# M703E.net
KiCad netlist of a schematic drawn in EAGLE
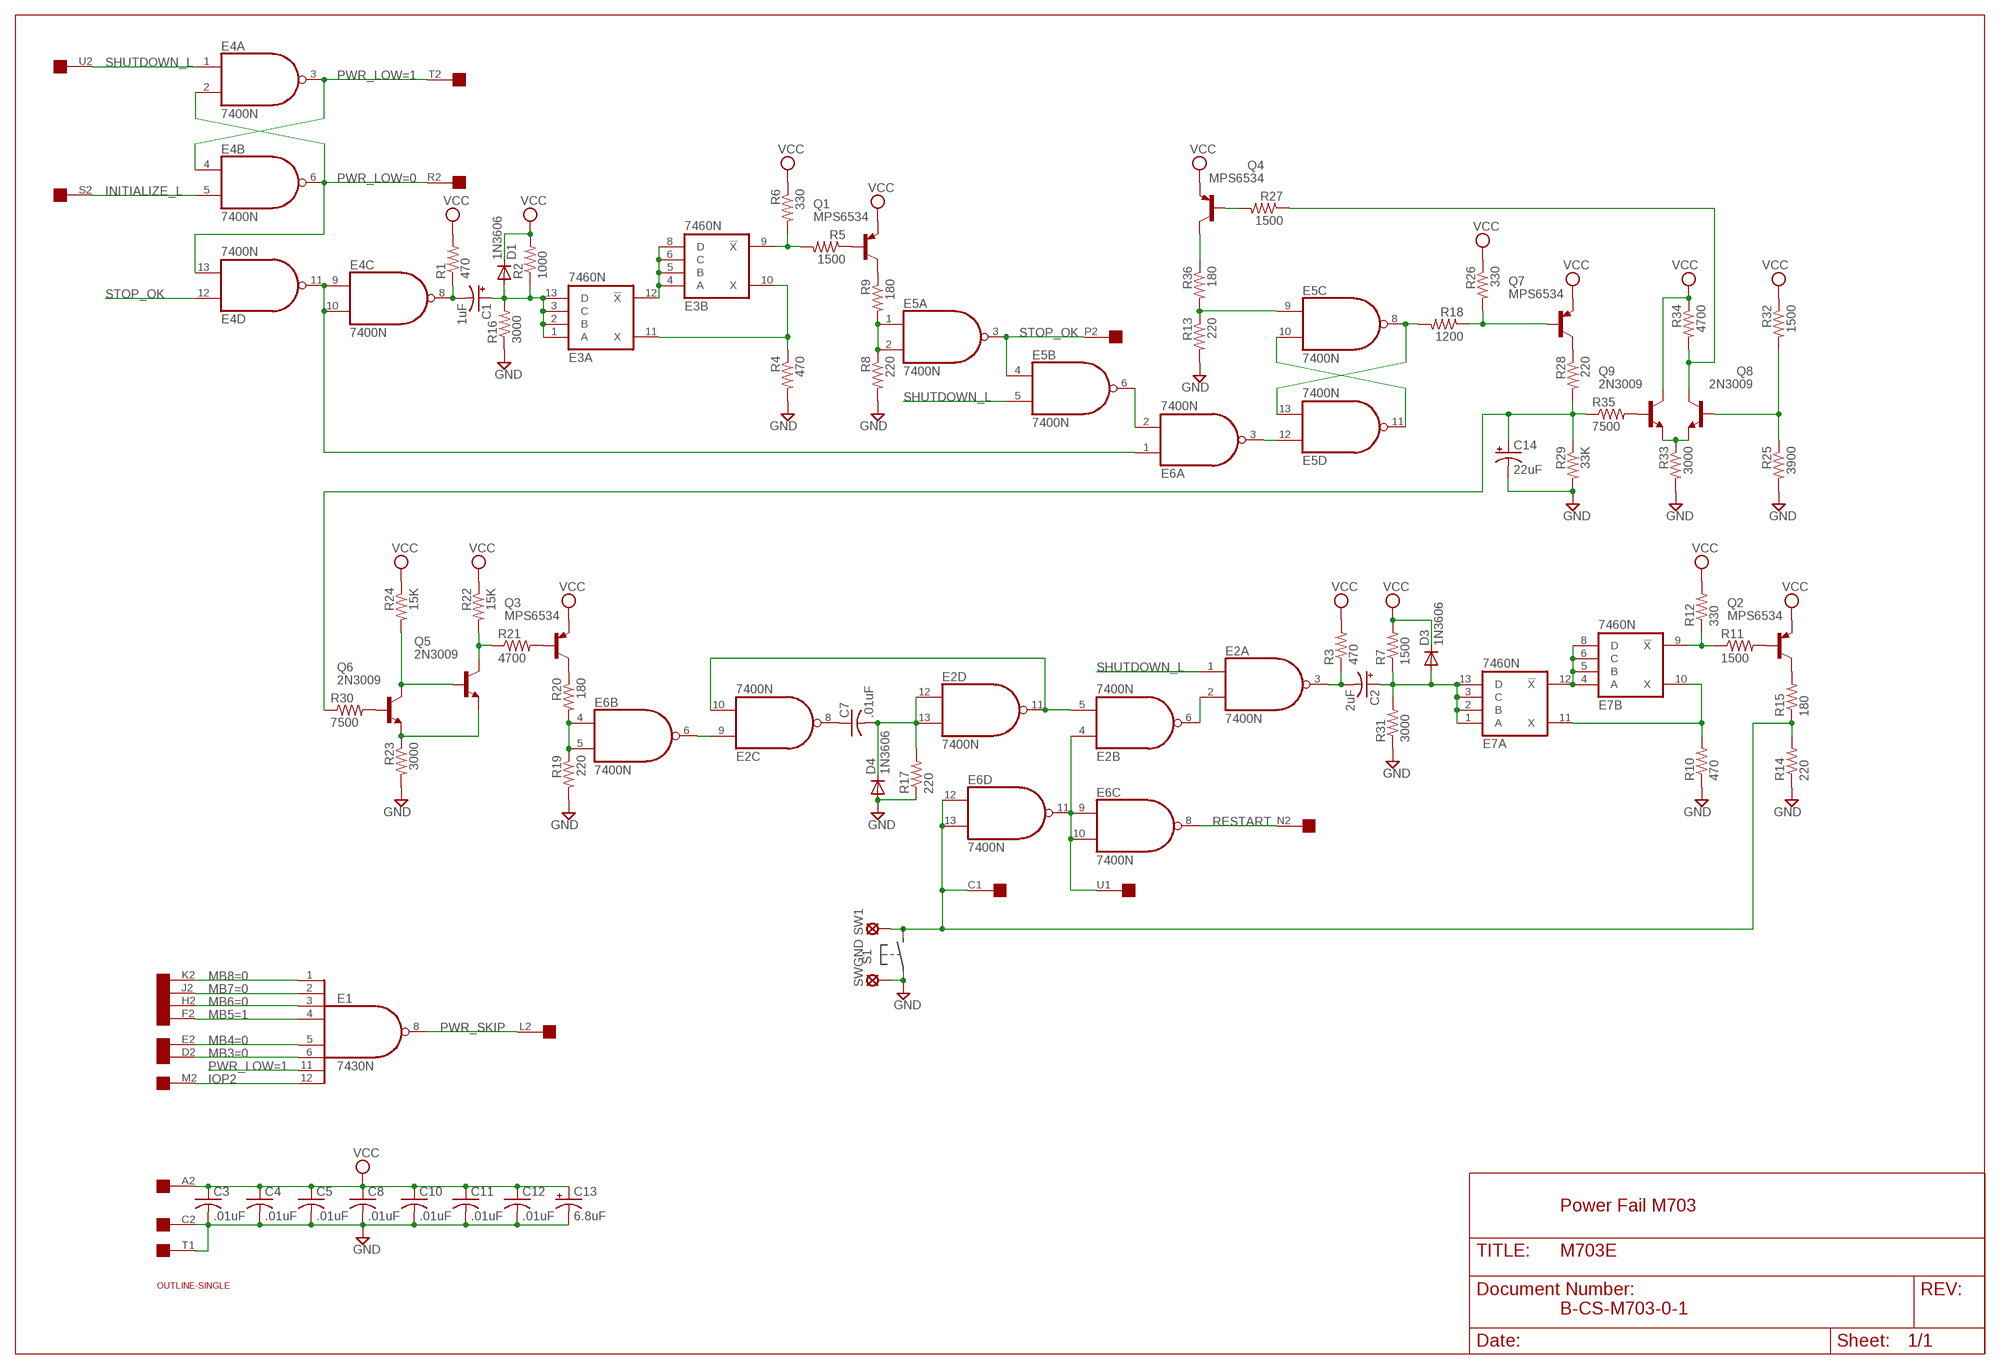
[diagram p0: schematic, sheet 1]

(export (version "E")
  (design (tool "Eeschema 10.0.6"))
  (components
    (comp (ref "C1")
      (value "1uF")
      (footprint "eagle-import:E12-4")
      (libsource (lib "eagle-import") (part "CPOL-USE12-4AXIAL"))
    )
    (comp (ref "C2")
      (value "2uF")
      (footprint "eagle-import:E12-4")
      (libsource (lib "eagle-import") (part "CPOL-USE12-4AXIAL"))
    )
    (comp (ref "C3")
      (value ".01uF")
      (footprint "eagle-import:C050-025X075")
      (libsource (lib "eagle-import") (part "C-US050-025X075"))
    )
    (comp (ref "C4")
      (value ".01uF")
      (footprint "eagle-import:C050-025X075")
      (libsource (lib "eagle-import") (part "C-US050-025X075"))
    )
    (comp (ref "C5")
      (value ".01uF")
      (footprint "eagle-import:C050-025X075")
      (libsource (lib "eagle-import") (part "C-US050-025X075"))
    )
    (comp (ref "C7")
      (value ".01uF")
      (footprint "eagle-import:C050-025X075")
      (libsource (lib "eagle-import") (part "C-US050-025X075"))
    )
    (comp (ref "C8")
      (value ".01uF")
      (footprint "eagle-import:C050-025X075")
      (libsource (lib "eagle-import") (part "C-US050-025X075"))
    )
    (comp (ref "C10")
      (value ".01uF")
      (footprint "eagle-import:C050-025X075")
      (libsource (lib "eagle-import") (part "C-US050-025X075"))
    )
    (comp (ref "C11")
      (value ".01uF")
      (footprint "eagle-import:C050-025X075")
      (libsource (lib "eagle-import") (part "C-US050-025X075"))
    )
    (comp (ref "C12")
      (value ".01uF")
      (footprint "eagle-import:C050-025X075")
      (libsource (lib "eagle-import") (part "C-US050-025X075"))
    )
    (comp (ref "C13")
      (value "6.8uF")
      (footprint "eagle-import:E15-5")
      (libsource (lib "eagle-import") (part "CPOL-USE15-5AXIAL"))
    )
    (comp (ref "C14")
      (value "22uF")
      (footprint "eagle-import:E15-5")
      (libsource (lib "eagle-import") (part "CPOL-USE15-5AXIAL"))
    )
    (comp (ref "D1")
      (value "1N3606")
      (footprint "eagle-import:DO35-10")
      (libsource (lib "eagle-import") (part "1N4148DO35-10"))
    )
    (comp (ref "D3")
      (value "1N3606")
      (footprint "eagle-import:DO35-10")
      (libsource (lib "eagle-import") (part "1N4148DO35-10"))
    )
    (comp (ref "D4")
      (value "1N3606")
      (footprint "eagle-import:DO35-10")
      (libsource (lib "eagle-import") (part "1N4148DO35-10"))
    )
    (comp (ref "E1")
      (value "7430N")
      (footprint "eagle-import:DIL14")
      (libsource (lib "eagle-import") (part "7430N"))
    )
    (comp (ref "E2")
      (value "7400N")
      (footprint "eagle-import:DIL14")
      (libsource (lib "eagle-import") (part "7400N"))
    )
    (comp (ref "E3")
      (value "7460N")
      (footprint "eagle-import:DIL14")
      (libsource (lib "eagle-import") (part "7460N"))
    )
    (comp (ref "E4")
      (value "7400N")
      (footprint "eagle-import:DIL14")
      (libsource (lib "eagle-import") (part "7400N"))
    )
    (comp (ref "E5")
      (value "7400N")
      (footprint "eagle-import:DIL14")
      (libsource (lib "eagle-import") (part "7400N"))
    )
    (comp (ref "E6")
      (value "7400N")
      (footprint "eagle-import:DIL14")
      (libsource (lib "eagle-import") (part "7400N"))
    )
    (comp (ref "E7")
      (value "7460N")
      (footprint "eagle-import:DIL14")
      (libsource (lib "eagle-import") (part "7460N"))
    )
    (comp (ref "Q1")
      (value "MPS6534")
      (footprint "eagle-import:TO39")
      (libsource (lib "eagle-import") (part "2N2904"))
    )
    (comp (ref "Q2")
      (value "MPS6534")
      (footprint "eagle-import:TO39")
      (libsource (lib "eagle-import") (part "2N2904"))
    )
    (comp (ref "Q3")
      (value "MPS6534")
      (footprint "eagle-import:TO39")
      (libsource (lib "eagle-import") (part "2N2904"))
    )
    (comp (ref "Q4")
      (value "MPS6534")
      (footprint "eagle-import:TO39")
      (libsource (lib "eagle-import") (part "2N2904"))
    )
    (comp (ref "Q5")
      (value "2N3009")
      (footprint "eagle-import:TO5")
      (libsource (lib "eagle-import") (part "2N2219"))
    )
    (comp (ref "Q6")
      (value "2N3009")
      (footprint "eagle-import:TO5")
      (libsource (lib "eagle-import") (part "2N2219"))
    )
    (comp (ref "Q7")
      (value "MPS6534")
      (footprint "eagle-import:TO39")
      (libsource (lib "eagle-import") (part "2N2904"))
    )
    (comp (ref "Q8")
      (value "2N3009")
      (footprint "eagle-import:TO5")
      (libsource (lib "eagle-import") (part "2N2219"))
    )
    (comp (ref "Q9")
      (value "2N3009")
      (footprint "eagle-import:TO5")
      (libsource (lib "eagle-import") (part "2N2219"))
    )
    (comp (ref "R1")
      (value "470")
      (footprint "eagle-import:0207_10")
      (libsource (lib "eagle-import") (part "R-US_0207/10"))
    )
    (comp (ref "R2")
      (value "1000")
      (footprint "eagle-import:0207_10")
      (libsource (lib "eagle-import") (part "R-US_0207/10"))
    )
    (comp (ref "R3")
      (value "470")
      (footprint "eagle-import:0207_10")
      (libsource (lib "eagle-import") (part "R-US_0207/10"))
    )
    (comp (ref "R4")
      (value "470")
      (footprint "eagle-import:0207_10")
      (libsource (lib "eagle-import") (part "R-US_0207/10"))
    )
    (comp (ref "R5")
      (value "1500")
      (footprint "eagle-import:0207_10")
      (libsource (lib "eagle-import") (part "R-US_0207/10"))
    )
    (comp (ref "R6")
      (value "330")
      (footprint "eagle-import:0207_10")
      (libsource (lib "eagle-import") (part "R-US_0207/10"))
    )
    (comp (ref "R7")
      (value "1500")
      (footprint "eagle-import:0207_10")
      (libsource (lib "eagle-import") (part "R-US_0207/10"))
    )
    (comp (ref "R8")
      (value "220")
      (footprint "eagle-import:0207_10")
      (libsource (lib "eagle-import") (part "R-US_0207/10"))
    )
    (comp (ref "R9")
      (value "180")
      (footprint "eagle-import:0207_10")
      (libsource (lib "eagle-import") (part "R-US_0207/10"))
    )
    (comp (ref "R10")
      (value "470")
      (footprint "eagle-import:0207_10")
      (libsource (lib "eagle-import") (part "R-US_0207/10"))
    )
    (comp (ref "R11")
      (value "1500")
      (footprint "eagle-import:0207_10")
      (libsource (lib "eagle-import") (part "R-US_0207/10"))
    )
    (comp (ref "R12")
      (value "330")
      (footprint "eagle-import:0207_10")
      (libsource (lib "eagle-import") (part "R-US_0207/10"))
    )
    (comp (ref "R13")
      (value "220")
      (footprint "eagle-import:0207_10")
      (libsource (lib "eagle-import") (part "R-US_0207/10"))
    )
    (comp (ref "R14")
      (value "220")
      (footprint "eagle-import:0207_10")
      (libsource (lib "eagle-import") (part "R-US_0207/10"))
    )
    (comp (ref "R15")
      (value "180")
      (footprint "eagle-import:0207_10")
      (libsource (lib "eagle-import") (part "R-US_0207/10"))
    )
    (comp (ref "R16")
      (value "3000")
      (footprint "eagle-import:0207_10")
      (libsource (lib "eagle-import") (part "R-US_0207/10"))
    )
    (comp (ref "R17")
      (value "220")
      (footprint "eagle-import:0207_10")
      (libsource (lib "eagle-import") (part "R-US_0207/10"))
    )
    (comp (ref "R18")
      (value "1200")
      (footprint "eagle-import:0207_10")
      (libsource (lib "eagle-import") (part "R-US_0207/10"))
    )
    (comp (ref "R19")
      (value "220")
      (footprint "eagle-import:0207_10")
      (libsource (lib "eagle-import") (part "R-US_0207/10"))
    )
    (comp (ref "R20")
      (value "180")
      (footprint "eagle-import:0207_10")
      (libsource (lib "eagle-import") (part "R-US_0207/10"))
    )
    (comp (ref "R21")
      (value "4700")
      (footprint "eagle-import:0207_10")
      (libsource (lib "eagle-import") (part "R-US_0207/10"))
    )
    (comp (ref "R22")
      (value "15K")
      (footprint "eagle-import:0207_10")
      (libsource (lib "eagle-import") (part "R-US_0207/10"))
    )
    (comp (ref "R23")
      (value "3000")
      (footprint "eagle-import:0207_10")
      (libsource (lib "eagle-import") (part "R-US_0207/10"))
    )
    (comp (ref "R24")
      (value "15K")
      (footprint "eagle-import:0207_10")
      (libsource (lib "eagle-import") (part "R-US_0207/10"))
    )
    (comp (ref "R25")
      (value "3900")
      (footprint "eagle-import:0207_10")
      (libsource (lib "eagle-import") (part "R-US_0207/10"))
    )
    (comp (ref "R26")
      (value "330")
      (footprint "eagle-import:0207_10")
      (libsource (lib "eagle-import") (part "R-US_0207/10"))
    )
    (comp (ref "R27")
      (value "1500")
      (footprint "eagle-import:0207_10")
      (libsource (lib "eagle-import") (part "R-US_0207/10"))
    )
    (comp (ref "R28")
      (value "220")
      (footprint "eagle-import:0207_10")
      (libsource (lib "eagle-import") (part "R-US_0207/10"))
    )
    (comp (ref "R29")
      (value "33K")
      (footprint "eagle-import:0207_10")
      (libsource (lib "eagle-import") (part "R-US_0207/10"))
    )
    (comp (ref "R30")
      (value "7500")
      (footprint "eagle-import:0207_10")
      (libsource (lib "eagle-import") (part "R-US_0207/10"))
    )
    (comp (ref "R31")
      (value "3000")
      (footprint "eagle-import:0207_10")
      (libsource (lib "eagle-import") (part "R-US_0207/10"))
    )
    (comp (ref "R32")
      (value "1500")
      (footprint "eagle-import:0207_10")
      (libsource (lib "eagle-import") (part "R-US_0207/10"))
    )
    (comp (ref "R33")
      (value "3000")
      (footprint "eagle-import:0207_10")
      (libsource (lib "eagle-import") (part "R-US_0207/10"))
    )
    (comp (ref "R34")
      (value "4700")
      (footprint "eagle-import:0207_10")
      (libsource (lib "eagle-import") (part "R-US_0207/10"))
    )
    (comp (ref "R35")
      (value "7500")
      (footprint "eagle-import:0207_10")
      (libsource (lib "eagle-import") (part "R-US_0207/10"))
    )
    (comp (ref "R36")
      (value "180")
      (footprint "eagle-import:0207_10")
      (libsource (lib "eagle-import") (part "R-US_0207/10"))
    )
    (comp (ref "SW1")
      (value "SE14")
      (footprint "eagle-import:SE14")
      (libsource (lib "eagle-import") (part "SE14"))
    )
    (comp (ref "SWGND")
      (value "SE14")
      (footprint "eagle-import:SE14")
      (libsource (lib "eagle-import") (part "SE14"))
    )
    (comp (ref "U$2")
      (value "SINGLE")
      (footprint "eagle-import:EDGE-CON2")
      (libsource (lib "eagle-import") (part "SINGLE"))
    )
    (comp (ref "U$4")
      (value "OUTLINE-SINGLE")
      (footprint "eagle-import:SINGLE")
      (libsource (lib "eagle-import") (part "OUTLINE-SINGLE"))
    )
  )
  (nets
    (net (code "1") (name "/INITIALIZE_L") (class "Default")
      (node (ref "E4") (pin "5") (pinfunction "I1_5") (pintype "input"))
      (node (ref "U$2") (pin "S2") (pinfunction "1_S2") (pintype "bidirectional"))
    )
    (net (code "2") (name "/IOP2") (class "Default")
      (node (ref "E1") (pin "12") (pinfunction "I7_12") (pintype "input"))
      (node (ref "U$2") (pin "M2") (pinfunction "1_M2") (pintype "bidirectional"))
    )
    (net (code "3") (name "/MB3=0") (class "Default")
      (node (ref "E1") (pin "6") (pinfunction "I5_6") (pintype "input"))
      (node (ref "U$2") (pin "D2") (pinfunction "1_D2") (pintype "bidirectional"))
    )
    (net (code "4") (name "/MB4=0") (class "Default")
      (node (ref "E1") (pin "5") (pinfunction "I4_5") (pintype "input"))
      (node (ref "U$2") (pin "E2") (pinfunction "1_E2") (pintype "bidirectional"))
    )
    (net (code "5") (name "/MB5=1") (class "Default")
      (node (ref "E1") (pin "4") (pinfunction "I3_4") (pintype "input"))
      (node (ref "U$2") (pin "F2") (pinfunction "1_F2") (pintype "bidirectional"))
    )
    (net (code "6") (name "/MB6=0") (class "Default")
      (node (ref "E1") (pin "3") (pinfunction "I2_3") (pintype "input"))
      (node (ref "U$2") (pin "H2") (pinfunction "1_H2") (pintype "bidirectional"))
    )
    (net (code "7") (name "/MB7=0") (class "Default")
      (node (ref "E1") (pin "2") (pinfunction "I1_2") (pintype "input"))
      (node (ref "U$2") (pin "J2") (pinfunction "1_J2") (pintype "bidirectional"))
    )
    (net (code "8") (name "/MB8=0") (class "Default")
      (node (ref "E1") (pin "1") (pinfunction "I0_1") (pintype "input"))
      (node (ref "U$2") (pin "K2") (pinfunction "1_K2") (pintype "bidirectional"))
    )
    (net (code "9") (name "/PWR_LOW=0") (class "Default")
      (node (ref "E4") (pin "13") (pinfunction "I1_13") (pintype "input"))
      (node (ref "E4") (pin "2") (pinfunction "I1_2") (pintype "input"))
      (node (ref "E4") (pin "6") (pinfunction "O_6") (pintype "output"))
      (node (ref "U$2") (pin "R2") (pinfunction "1_R2") (pintype "bidirectional"))
    )
    (net (code "10") (name "/PWR_LOW=1") (class "Default")
      (node (ref "E1") (pin "11") (pinfunction "I6_11") (pintype "input"))
      (node (ref "E4") (pin "3") (pinfunction "O_3") (pintype "output"))
      (node (ref "E4") (pin "4") (pinfunction "I0_4") (pintype "input"))
      (node (ref "U$2") (pin "T2") (pinfunction "1_T2") (pintype "bidirectional"))
    )
    (net (code "11") (name "/PWR_SKIP") (class "Default")
      (node (ref "E1") (pin "8") (pinfunction "O_8") (pintype "output"))
      (node (ref "U$2") (pin "L2") (pinfunction "1_L2") (pintype "bidirectional"))
    )
    (net (code "12") (name "/RESTART") (class "Default")
      (node (ref "E6") (pin "8") (pinfunction "O_8") (pintype "output"))
      (node (ref "U$2") (pin "N2") (pinfunction "1_N2") (pintype "bidirectional"))
    )
    (net (code "13") (name "/SHUTDOWN_L") (class "Default")
      (node (ref "E2") (pin "1") (pinfunction "I0_1") (pintype "input"))
      (node (ref "E4") (pin "1") (pinfunction "I0_1") (pintype "input"))
      (node (ref "E5") (pin "5") (pinfunction "I1_5") (pintype "input"))
      (node (ref "U$2") (pin "U2") (pinfunction "1_U2") (pintype "bidirectional"))
    )
    (net (code "14") (name "/STOP_OK") (class "Default")
      (node (ref "E4") (pin "12") (pinfunction "I0_12") (pintype "input"))
      (node (ref "E5") (pin "3") (pinfunction "O_3") (pintype "output"))
      (node (ref "E5") (pin "4") (pinfunction "I0_4") (pintype "input"))
      (node (ref "U$2") (pin "P2") (pinfunction "1_P2") (pintype "bidirectional"))
    )
    (net (code "15") (name "GND") (class "Default")
      (node (ref "C10") (pin "2") (pinfunction "2_2") (pintype "passive"))
      (node (ref "C11") (pin "2") (pinfunction "2_2") (pintype "passive"))
      (node (ref "C12") (pin "2") (pinfunction "2_2") (pintype "passive"))
      (node (ref "C13") (pin "-") (pinfunction "-_-") (pintype "passive"))
      (node (ref "C14") (pin "-") (pinfunction "-_-") (pintype "passive"))
      (node (ref "C3") (pin "2") (pinfunction "2_2") (pintype "passive"))
      (node (ref "C4") (pin "2") (pinfunction "2_2") (pintype "passive"))
      (node (ref "C5") (pin "2") (pinfunction "2_2") (pintype "passive"))
      (node (ref "C8") (pin "2") (pinfunction "2_2") (pintype "passive"))
      (node (ref "D4") (pin "A") (pinfunction "A_A") (pintype "passive"))
      (node (ref "R10") (pin "1") (pinfunction "1_1") (pintype "passive"))
      (node (ref "R13") (pin "2") (pinfunction "2_2") (pintype "passive"))
      (node (ref "R14") (pin "1") (pinfunction "1_1") (pintype "passive"))
      (node (ref "R16") (pin "1") (pinfunction "1_1") (pintype "passive"))
      (node (ref "R17") (pin "1") (pinfunction "1_1") (pintype "passive"))
      (node (ref "R19") (pin "2") (pinfunction "2_2") (pintype "passive"))
      (node (ref "R23") (pin "2") (pinfunction "2_2") (pintype "passive"))
      (node (ref "R25") (pin "2") (pinfunction "2_2") (pintype "passive"))
      (node (ref "R29") (pin "2") (pinfunction "2_2") (pintype "passive"))
      (node (ref "R31") (pin "1") (pinfunction "1_1") (pintype "passive"))
      (node (ref "R33") (pin "2") (pinfunction "2_2") (pintype "passive"))
      (node (ref "R4") (pin "2") (pinfunction "2_2") (pintype "passive"))
      (node (ref "R8") (pin "2") (pinfunction "2_2") (pintype "passive"))
      (node (ref "SWGND") (pin "MP") (pinfunction "MP_MP") (pintype "passive"))
      (node (ref "U$2") (pin "C2") (pinfunction "1_C2") (pintype "bidirectional"))
      (node (ref "U$2") (pin "T1") (pinfunction "1_T1") (pintype "bidirectional"))
    )
    (net (code "16") (name "Net-(C14-Pad+)") (class "Default")
      (node (ref "C14") (pin "+") (pinfunction "+_+") (pintype "passive"))
      (node (ref "R28") (pin "2") (pinfunction "2_2") (pintype "passive"))
      (node (ref "R29") (pin "1") (pinfunction "1_1") (pintype "passive"))
      (node (ref "R30") (pin "1") (pinfunction "1_1") (pintype "passive"))
      (node (ref "R35") (pin "1") (pinfunction "1_1") (pintype "passive"))
    )
    (net (code "17") (name "Net-(E2A-I1)") (class "Default")
      (node (ref "E2") (pin "2") (pinfunction "I1_2") (pintype "input"))
      (node (ref "E2") (pin "6") (pinfunction "O_6") (pintype "output"))
    )
    (net (code "18") (name "Net-(E2A-O)") (class "Default")
      (node (ref "C2") (pin "-") (pinfunction "-_-") (pintype "passive"))
      (node (ref "E2") (pin "3") (pinfunction "O_3") (pintype "output"))
      (node (ref "R3") (pin "1") (pinfunction "1_1") (pintype "passive"))
    )
    (net (code "19") (name "Net-(E2B-I0)") (class "Default")
      (node (ref "E2") (pin "4") (pinfunction "I0_4") (pintype "input"))
      (node (ref "E6") (pin "10") (pinfunction "I1_10") (pintype "input"))
      (node (ref "E6") (pin "11") (pinfunction "O_11") (pintype "output"))
      (node (ref "E6") (pin "9") (pinfunction "I0_9") (pintype "input"))
      (node (ref "U$2") (pin "U1") (pinfunction "1_U1") (pintype "bidirectional"))
    )
    (net (code "20") (name "Net-(E2B-I1)") (class "Default")
      (node (ref "E2") (pin "10") (pinfunction "I1_10") (pintype "input"))
      (node (ref "E2") (pin "11") (pinfunction "O_11") (pintype "output"))
      (node (ref "E2") (pin "5") (pinfunction "I1_5") (pintype "input"))
    )
    (net (code "21") (name "Net-(E2C-I0)") (class "Default")
      (node (ref "E2") (pin "9") (pinfunction "I0_9") (pintype "input"))
      (node (ref "E6") (pin "6") (pinfunction "O_6") (pintype "output"))
    )
    (net (code "22") (name "Net-(E2C-O)") (class "Default")
      (node (ref "C7") (pin "1") (pinfunction "1_1") (pintype "passive"))
      (node (ref "E2") (pin "8") (pinfunction "O_8") (pintype "output"))
    )
    (net (code "23") (name "Net-(E2D-I0)") (class "Default")
      (node (ref "C7") (pin "2") (pinfunction "2_2") (pintype "passive"))
      (node (ref "D4") (pin "C") (pinfunction "C_C") (pintype "passive"))
      (node (ref "E2") (pin "12") (pinfunction "I0_12") (pintype "input"))
      (node (ref "E2") (pin "13") (pinfunction "I1_13") (pintype "input"))
      (node (ref "R17") (pin "2") (pinfunction "2_2") (pintype "passive"))
    )
    (net (code "24") (name "Net-(E3A-A)") (class "Default")
      (node (ref "C1") (pin "+") (pinfunction "+_+") (pintype "passive"))
      (node (ref "D1") (pin "A") (pinfunction "A_A") (pintype "passive"))
      (node (ref "E3") (pin "1") (pinfunction "A_1") (pintype "input"))
      (node (ref "E3") (pin "13") (pinfunction "D_13") (pintype "input"))
      (node (ref "E3") (pin "2") (pinfunction "B_2") (pintype "input"))
      (node (ref "E3") (pin "3") (pinfunction "C_3") (pintype "input"))
      (node (ref "R16") (pin "2") (pinfunction "2_2") (pintype "passive"))
      (node (ref "R2") (pin "1") (pinfunction "1_1") (pintype "passive"))
    )
    (net (code "25") (name "Net-(E3A-X)") (class "Default")
      (node (ref "E3") (pin "10") (pinfunction "X_10") (pintype "output"))
      (node (ref "E3") (pin "11") (pinfunction "X_11") (pintype "output"))
      (node (ref "R4") (pin "1") (pinfunction "1_1") (pintype "passive"))
    )
    (net (code "26") (name "Net-(E3A-~{X})") (class "Default")
      (node (ref "E3") (pin "12") (pinfunction "~{X}_12") (pintype "output"))
      (node (ref "E3") (pin "4") (pinfunction "A_4") (pintype "input"))
      (node (ref "E3") (pin "5") (pinfunction "B_5") (pintype "input"))
      (node (ref "E3") (pin "6") (pinfunction "C_6") (pintype "input"))
      (node (ref "E3") (pin "8") (pinfunction "D_8") (pintype "input"))
    )
    (net (code "27") (name "Net-(E3B-~{X})") (class "Default")
      (node (ref "E3") (pin "9") (pinfunction "~{X}_9") (pintype "output"))
      (node (ref "R5") (pin "2") (pinfunction "2_2") (pintype "passive"))
      (node (ref "R6") (pin "2") (pinfunction "2_2") (pintype "passive"))
    )
    (net (code "28") (name "Net-(E4C-I0)") (class "Default")
      (node (ref "E4") (pin "10") (pinfunction "I1_10") (pintype "input"))
      (node (ref "E4") (pin "11") (pinfunction "O_11") (pintype "output"))
      (node (ref "E4") (pin "9") (pinfunction "I0_9") (pintype "input"))
      (node (ref "E6") (pin "1") (pinfunction "I0_1") (pintype "input"))
    )
    (net (code "29") (name "Net-(E4C-O)") (class "Default")
      (node (ref "C1") (pin "-") (pinfunction "-_-") (pintype "passive"))
      (node (ref "E4") (pin "8") (pinfunction "O_8") (pintype "output"))
      (node (ref "R1") (pin "1") (pinfunction "1_1") (pintype "passive"))
    )
    (net (code "30") (name "Net-(E5A-I0)") (class "Default")
      (node (ref "E5") (pin "1") (pinfunction "I0_1") (pintype "input"))
      (node (ref "E5") (pin "2") (pinfunction "I1_2") (pintype "input"))
      (node (ref "R8") (pin "1") (pinfunction "1_1") (pintype "passive"))
      (node (ref "R9") (pin "2") (pinfunction "2_2") (pintype "passive"))
    )
    (net (code "31") (name "Net-(E5B-O)") (class "Default")
      (node (ref "E5") (pin "6") (pinfunction "O_6") (pintype "output"))
      (node (ref "E6") (pin "2") (pinfunction "I1_2") (pintype "input"))
    )
    (net (code "32") (name "Net-(E5C-I0)") (class "Default")
      (node (ref "E5") (pin "9") (pinfunction "I0_9") (pintype "input"))
      (node (ref "R13") (pin "1") (pinfunction "1_1") (pintype "passive"))
      (node (ref "R36") (pin "2") (pinfunction "2_2") (pintype "passive"))
    )
    (net (code "33") (name "Net-(E5C-I1)") (class "Default")
      (node (ref "E5") (pin "10") (pinfunction "I1_10") (pintype "input"))
      (node (ref "E5") (pin "11") (pinfunction "O_11") (pintype "output"))
    )
    (net (code "34") (name "Net-(E5C-O)") (class "Default")
      (node (ref "E5") (pin "13") (pinfunction "I1_13") (pintype "input"))
      (node (ref "E5") (pin "8") (pinfunction "O_8") (pintype "output"))
      (node (ref "R18") (pin "2") (pinfunction "2_2") (pintype "passive"))
    )
    (net (code "35") (name "Net-(E5D-I0)") (class "Default")
      (node (ref "E5") (pin "12") (pinfunction "I0_12") (pintype "input"))
      (node (ref "E6") (pin "3") (pinfunction "O_3") (pintype "output"))
    )
    (net (code "36") (name "Net-(E6B-I0)") (class "Default")
      (node (ref "E6") (pin "4") (pinfunction "I0_4") (pintype "input"))
      (node (ref "E6") (pin "5") (pinfunction "I1_5") (pintype "input"))
      (node (ref "R19") (pin "1") (pinfunction "1_1") (pintype "passive"))
      (node (ref "R20") (pin "2") (pinfunction "2_2") (pintype "passive"))
    )
    (net (code "37") (name "Net-(E6D-I0)") (class "Default")
      (node (ref "E6") (pin "12") (pinfunction "I0_12") (pintype "input"))
      (node (ref "E6") (pin "13") (pinfunction "I1_13") (pintype "input"))
      (node (ref "R14") (pin "2") (pinfunction "2_2") (pintype "passive"))
      (node (ref "R15") (pin "1") (pinfunction "1_1") (pintype "passive"))
      (node (ref "SW1") (pin "MP") (pinfunction "MP_MP") (pintype "passive"))
      (node (ref "U$2") (pin "C1") (pinfunction "1_C1") (pintype "bidirectional"))
    )
    (net (code "38") (name "Net-(E7A-A)") (class "Default")
      (node (ref "C2") (pin "+") (pinfunction "+_+") (pintype "passive"))
      (node (ref "D3") (pin "A") (pinfunction "A_A") (pintype "passive"))
      (node (ref "E7") (pin "1") (pinfunction "A_1") (pintype "input"))
      (node (ref "E7") (pin "13") (pinfunction "D_13") (pintype "input"))
      (node (ref "E7") (pin "2") (pinfunction "B_2") (pintype "input"))
      (node (ref "E7") (pin "3") (pinfunction "C_3") (pintype "input"))
      (node (ref "R31") (pin "2") (pinfunction "2_2") (pintype "passive"))
      (node (ref "R7") (pin "1") (pinfunction "1_1") (pintype "passive"))
    )
    (net (code "39") (name "Net-(E7A-X)") (class "Default")
      (node (ref "E7") (pin "10") (pinfunction "X_10") (pintype "output"))
      (node (ref "E7") (pin "11") (pinfunction "X_11") (pintype "output"))
      (node (ref "R10") (pin "2") (pinfunction "2_2") (pintype "passive"))
    )
    (net (code "40") (name "Net-(E7A-~{X})") (class "Default")
      (node (ref "E7") (pin "12") (pinfunction "~{X}_12") (pintype "output"))
      (node (ref "E7") (pin "4") (pinfunction "A_4") (pintype "input"))
      (node (ref "E7") (pin "5") (pinfunction "B_5") (pintype "input"))
      (node (ref "E7") (pin "6") (pinfunction "C_6") (pintype "input"))
      (node (ref "E7") (pin "8") (pinfunction "D_8") (pintype "input"))
    )
    (net (code "41") (name "Net-(E7B-~{X})") (class "Default")
      (node (ref "E7") (pin "9") (pinfunction "~{X}_9") (pintype "output"))
      (node (ref "R11") (pin "1") (pinfunction "1_1") (pintype "passive"))
      (node (ref "R12") (pin "1") (pinfunction "1_1") (pintype "passive"))
    )
    (net (code "42") (name "Net-(Q1-B)") (class "Default")
      (node (ref "Q1") (pin "2") (pinfunction "B_2") (pintype "passive"))
      (node (ref "R5") (pin "1") (pinfunction "1_1") (pintype "passive"))
    )
    (net (code "43") (name "Net-(Q1-C)") (class "Default")
      (node (ref "Q1") (pin "3") (pinfunction "C_3") (pintype "passive"))
      (node (ref "R9") (pin "1") (pinfunction "1_1") (pintype "passive"))
    )
    (net (code "44") (name "Net-(Q2-B)") (class "Default")
      (node (ref "Q2") (pin "2") (pinfunction "B_2") (pintype "passive"))
      (node (ref "R11") (pin "2") (pinfunction "2_2") (pintype "passive"))
    )
    (net (code "45") (name "Net-(Q2-C)") (class "Default")
      (node (ref "Q2") (pin "3") (pinfunction "C_3") (pintype "passive"))
      (node (ref "R15") (pin "2") (pinfunction "2_2") (pintype "passive"))
    )
    (net (code "46") (name "Net-(Q3-B)") (class "Default")
      (node (ref "Q3") (pin "2") (pinfunction "B_2") (pintype "passive"))
      (node (ref "R21") (pin "2") (pinfunction "2_2") (pintype "passive"))
    )
    (net (code "47") (name "Net-(Q3-C)") (class "Default")
      (node (ref "Q3") (pin "3") (pinfunction "C_3") (pintype "passive"))
      (node (ref "R20") (pin "1") (pinfunction "1_1") (pintype "passive"))
    )
    (net (code "48") (name "Net-(Q4-B)") (class "Default")
      (node (ref "Q4") (pin "2") (pinfunction "B_2") (pintype "passive"))
      (node (ref "R27") (pin "2") (pinfunction "2_2") (pintype "passive"))
    )
    (net (code "49") (name "Net-(Q4-C)") (class "Default")
      (node (ref "Q4") (pin "3") (pinfunction "C_3") (pintype "passive"))
      (node (ref "R36") (pin "1") (pinfunction "1_1") (pintype "passive"))
    )
    (net (code "50") (name "Net-(Q5-B)") (class "Default")
      (node (ref "Q5") (pin "2") (pinfunction "B_2") (pintype "passive"))
      (node (ref "Q6") (pin "3") (pinfunction "C_3") (pintype "passive"))
      (node (ref "R24") (pin "2") (pinfunction "2_2") (pintype "passive"))
    )
    (net (code "51") (name "Net-(Q5-C)") (class "Default")
      (node (ref "Q5") (pin "3") (pinfunction "C_3") (pintype "passive"))
      (node (ref "R21") (pin "1") (pinfunction "1_1") (pintype "passive"))
      (node (ref "R22") (pin "2") (pinfunction "2_2") (pintype "passive"))
    )
    (net (code "52") (name "Net-(Q5-E)") (class "Default")
      (node (ref "Q5") (pin "1") (pinfunction "E_1") (pintype "passive"))
      (node (ref "Q6") (pin "1") (pinfunction "E_1") (pintype "passive"))
      (node (ref "R23") (pin "1") (pinfunction "1_1") (pintype "passive"))
    )
    (net (code "53") (name "Net-(Q6-B)") (class "Default")
      (node (ref "Q6") (pin "2") (pinfunction "B_2") (pintype "passive"))
      (node (ref "R30") (pin "2") (pinfunction "2_2") (pintype "passive"))
    )
    (net (code "54") (name "Net-(Q7-B)") (class "Default")
      (node (ref "Q7") (pin "2") (pinfunction "B_2") (pintype "passive"))
      (node (ref "R18") (pin "1") (pinfunction "1_1") (pintype "passive"))
      (node (ref "R26") (pin "2") (pinfunction "2_2") (pintype "passive"))
    )
    (net (code "55") (name "Net-(Q7-C)") (class "Default")
      (node (ref "Q7") (pin "3") (pinfunction "C_3") (pintype "passive"))
      (node (ref "R28") (pin "1") (pinfunction "1_1") (pintype "passive"))
    )
    (net (code "56") (name "Net-(Q8-B)") (class "Default")
      (node (ref "Q8") (pin "2") (pinfunction "B_2") (pintype "passive"))
      (node (ref "R25") (pin "1") (pinfunction "1_1") (pintype "passive"))
      (node (ref "R32") (pin "2") (pinfunction "2_2") (pintype "passive"))
    )
    (net (code "57") (name "Net-(Q8-C)") (class "Default")
      (node (ref "Q8") (pin "3") (pinfunction "C_3") (pintype "passive"))
      (node (ref "R27") (pin "1") (pinfunction "1_1") (pintype "passive"))
      (node (ref "R34") (pin "2") (pinfunction "2_2") (pintype "passive"))
    )
    (net (code "58") (name "Net-(Q8-E)") (class "Default")
      (node (ref "Q8") (pin "1") (pinfunction "E_1") (pintype "passive"))
      (node (ref "Q9") (pin "1") (pinfunction "E_1") (pintype "passive"))
      (node (ref "R33") (pin "1") (pinfunction "1_1") (pintype "passive"))
    )
    (net (code "59") (name "Net-(Q9-B)") (class "Default")
      (node (ref "Q9") (pin "2") (pinfunction "B_2") (pintype "passive"))
      (node (ref "R35") (pin "2") (pinfunction "2_2") (pintype "passive"))
    )
    (net (code "60") (name "VCC") (class "Default")
      (node (ref "C10") (pin "1") (pinfunction "1_1") (pintype "passive"))
      (node (ref "C11") (pin "1") (pinfunction "1_1") (pintype "passive"))
      (node (ref "C12") (pin "1") (pinfunction "1_1") (pintype "passive"))
      (node (ref "C13") (pin "+") (pinfunction "+_+") (pintype "passive"))
      (node (ref "C3") (pin "1") (pinfunction "1_1") (pintype "passive"))
      (node (ref "C4") (pin "1") (pinfunction "1_1") (pintype "passive"))
      (node (ref "C5") (pin "1") (pinfunction "1_1") (pintype "passive"))
      (node (ref "C8") (pin "1") (pinfunction "1_1") (pintype "passive"))
      (node (ref "D1") (pin "C") (pinfunction "C_C") (pintype "passive"))
      (node (ref "D3") (pin "C") (pinfunction "C_C") (pintype "passive"))
      (node (ref "Q1") (pin "1") (pinfunction "E_1") (pintype "passive"))
      (node (ref "Q2") (pin "1") (pinfunction "E_1") (pintype "passive"))
      (node (ref "Q3") (pin "1") (pinfunction "E_1") (pintype "passive"))
      (node (ref "Q4") (pin "1") (pinfunction "E_1") (pintype "passive"))
      (node (ref "Q7") (pin "1") (pinfunction "E_1") (pintype "passive"))
      (node (ref "Q9") (pin "3") (pinfunction "C_3") (pintype "passive"))
      (node (ref "R1") (pin "2") (pinfunction "2_2") (pintype "passive"))
      (node (ref "R12") (pin "2") (pinfunction "2_2") (pintype "passive"))
      (node (ref "R2") (pin "2") (pinfunction "2_2") (pintype "passive"))
      (node (ref "R22") (pin "1") (pinfunction "1_1") (pintype "passive"))
      (node (ref "R24") (pin "1") (pinfunction "1_1") (pintype "passive"))
      (node (ref "R26") (pin "1") (pinfunction "1_1") (pintype "passive"))
      (node (ref "R3") (pin "2") (pinfunction "2_2") (pintype "passive"))
      (node (ref "R32") (pin "1") (pinfunction "1_1") (pintype "passive"))
      (node (ref "R34") (pin "1") (pinfunction "1_1") (pintype "passive"))
      (node (ref "R6") (pin "1") (pinfunction "1_1") (pintype "passive"))
      (node (ref "R7") (pin "2") (pinfunction "2_2") (pintype "passive"))
      (node (ref "U$2") (pin "A2") (pinfunction "1_A2") (pintype "bidirectional"))
    )
  )
)
